# Teensy_Hookup.net
KiCad netlist of a schematic drawn in Altium Designer
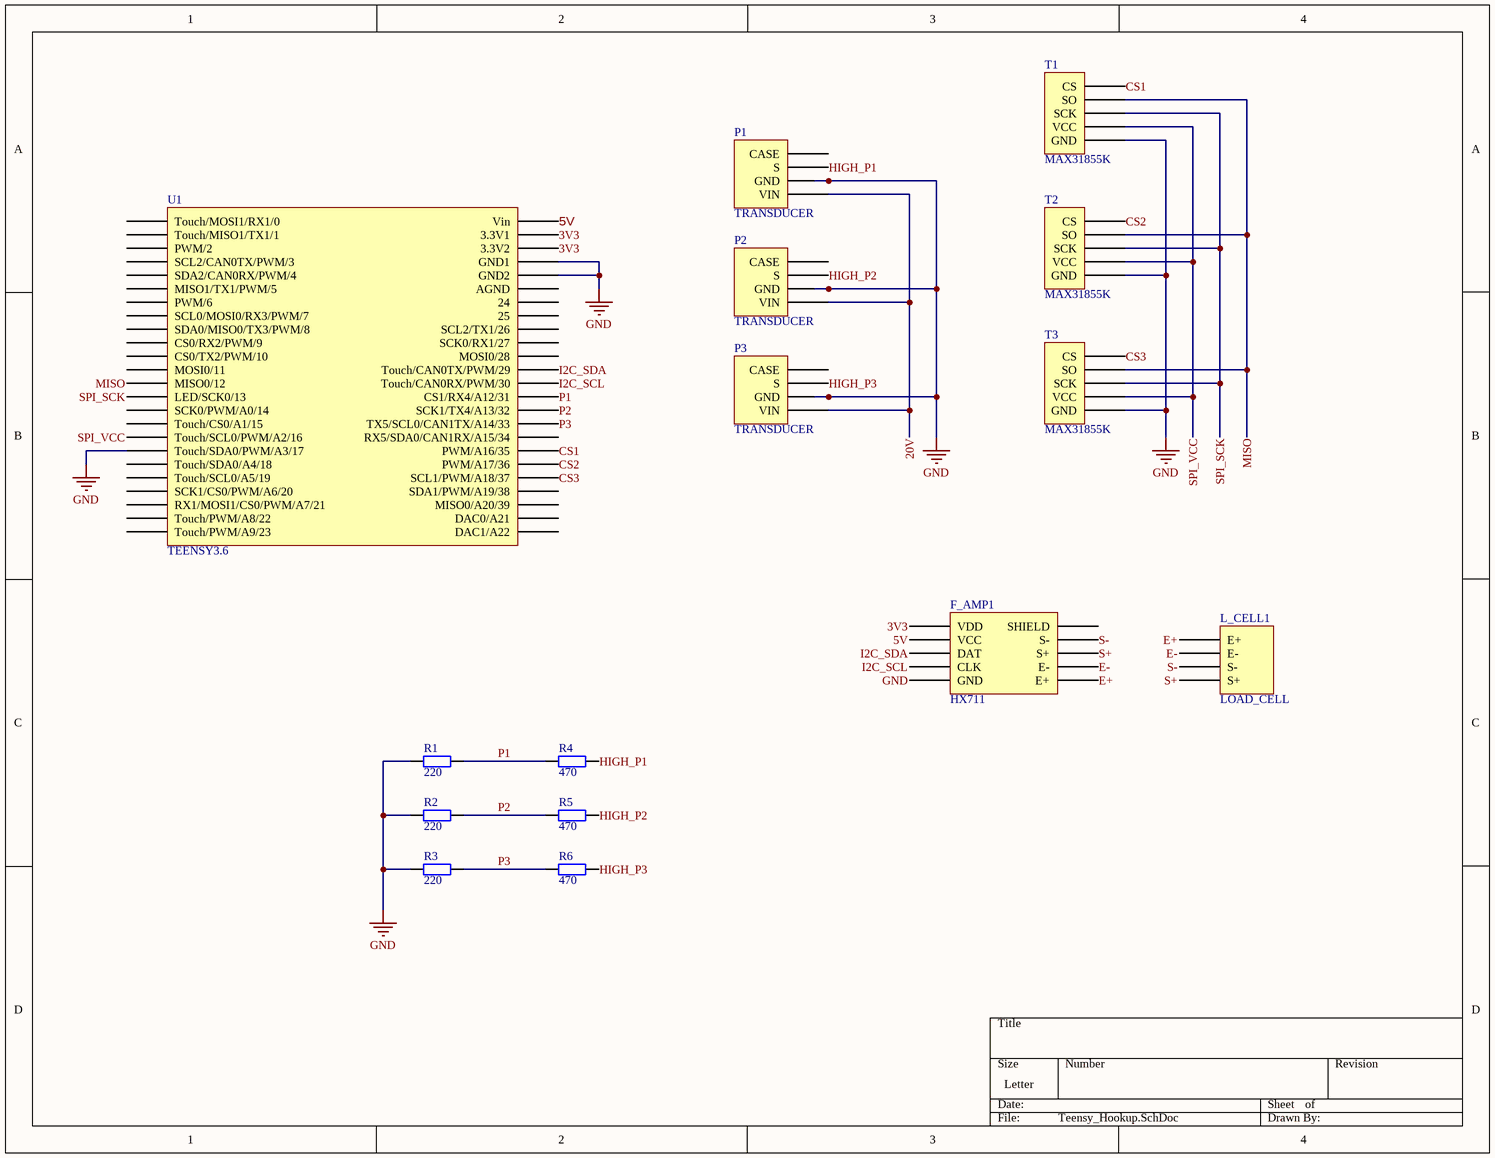
[diagram p0: Teensy_Hookup.SchDoc]

(export (version "E")
  (design (tool "Eeschema 10.0.6"))
  (components
    (comp (ref "F_AMP1") (value "HX711") (libsource (lib "components") (part "HX711")))
    (comp (ref "L_CELL1") (value "LOAD_CELL") (libsource (lib "components") (part "LOAD_CELL")))
    (comp (ref "P1") (value "TRANSDUCER") (libsource (lib "components") (part "TRANSDUCER")))
    (comp (ref "P2") (value "TRANSDUCER") (libsource (lib "components") (part "TRANSDUCER")))
    (comp (ref "P3") (value "TRANSDUCER") (libsource (lib "components") (part "TRANSDUCER")))
    (comp (ref "R1")
      (value "220")
      (footprint "AXIAL-0.4")
      (description "Resistor")
      (fields (field (name "PUBLISHER") "Altium Limited"))
      (libsource (lib "Miscellaneous Devices") (part "Res2"))
    )
    (comp (ref "R2")
      (value "220")
      (footprint "AXIAL-0.4")
      (description "Resistor")
      (fields (field (name "PUBLISHER") "Altium Limited"))
      (libsource (lib "Miscellaneous Devices") (part "Res2"))
    )
    (comp (ref "R3")
      (value "220")
      (footprint "AXIAL-0.4")
      (description "Resistor")
      (fields (field (name "PUBLISHER") "Altium Limited"))
      (libsource (lib "Miscellaneous Devices") (part "Res2"))
    )
    (comp (ref "R4")
      (value "470")
      (footprint "AXIAL-0.4")
      (description "Resistor")
      (fields (field (name "PUBLISHER") "Altium Limited"))
      (libsource (lib "Miscellaneous Devices") (part "Res2"))
    )
    (comp (ref "R5")
      (value "470")
      (footprint "AXIAL-0.4")
      (description "Resistor")
      (fields (field (name "PUBLISHER") "Altium Limited"))
      (libsource (lib "Miscellaneous Devices") (part "Res2"))
    )
    (comp (ref "R6")
      (value "470")
      (footprint "AXIAL-0.4")
      (description "Resistor")
      (fields (field (name "PUBLISHER") "Altium Limited"))
      (libsource (lib "Miscellaneous Devices") (part "Res2"))
    )
    (comp (ref "T1") (value "MAX31855K") (libsource (lib "components") (part "MAX31855K")))
    (comp (ref "T2") (value "MAX31855K") (libsource (lib "components") (part "MAX31855K")))
    (comp (ref "T3") (value "MAX31855K") (libsource (lib "components") (part "MAX31855K")))
    (comp (ref "U1") (value "TEENSY3.6") (libsource (lib "components") (part "TEENSY3.6")))
  )
  (nets
    (net (code "1") (name "/3V3") (class "Default")
      (node (ref "F_AMP1") (pin "1") (pinfunction "VDD_1") (pintype "passive"))
      (node (ref "U1") (pin "3.3V1") (pinfunction "3.3V1_3.3V1") (pintype "power_in"))
      (node (ref "U1") (pin "3.3V2") (pinfunction "3.3V2_3.3V2") (pintype "power_in"))
    )
    (net (code "2") (name "/5V") (class "Default")
      (node (ref "F_AMP1") (pin "2") (pinfunction "VCC_2") (pintype "passive"))
      (node (ref "U1") (pin "VIN") (pinfunction "Vin_VIN") (pintype "power_in"))
    )
    (net (code "3") (name "/20V") (class "Default")
      (node (ref "P1") (pin "1") (pinfunction "VIN_1") (pintype "passive"))
      (node (ref "P2") (pin "1") (pinfunction "VIN_1") (pintype "passive"))
      (node (ref "P3") (pin "1") (pinfunction "VIN_1") (pintype "passive"))
    )
    (net (code "4") (name "/CS1") (class "Default")
      (node (ref "T1") (pin "5") (pinfunction "CS_5") (pintype "passive"))
      (node (ref "U1") (pin "35") (pinfunction "PWM/A16/35_35") (pintype "passive"))
    )
    (net (code "5") (name "/CS2") (class "Default")
      (node (ref "T2") (pin "5") (pinfunction "CS_5") (pintype "passive"))
      (node (ref "U1") (pin "36") (pinfunction "PWM/A17/36_36") (pintype "passive"))
    )
    (net (code "6") (name "/CS3") (class "Default")
      (node (ref "T3") (pin "5") (pinfunction "CS_5") (pintype "passive"))
      (node (ref "U1") (pin "37") (pinfunction "SCL1/PWM/A18/37_37") (pintype "passive"))
    )
    (net (code "7") (name "/E+") (class "Default")
      (node (ref "F_AMP1") (pin "6") (pinfunction "E+_6") (pintype "passive"))
      (node (ref "L_CELL1") (pin "1") (pinfunction "E+_1") (pintype "passive"))
    )
    (net (code "8") (name "/E-") (class "Default")
      (node (ref "F_AMP1") (pin "7") (pinfunction "E-_7") (pintype "passive"))
      (node (ref "L_CELL1") (pin "2") (pinfunction "E-_2") (pintype "passive"))
    )
    (net (code "9") (name "/HIGH_P1") (class "Default")
      (node (ref "P1") (pin "3") (pinfunction "S_3") (pintype "passive"))
      (node (ref "R4") (pin "2") (pinfunction "2_2") (pintype "passive"))
    )
    (net (code "10") (name "/HIGH_P2") (class "Default")
      (node (ref "P2") (pin "3") (pinfunction "S_3") (pintype "passive"))
      (node (ref "R5") (pin "2") (pinfunction "2_2") (pintype "passive"))
    )
    (net (code "11") (name "/HIGH_P3") (class "Default")
      (node (ref "P3") (pin "3") (pinfunction "S_3") (pintype "passive"))
      (node (ref "R6") (pin "2") (pinfunction "2_2") (pintype "passive"))
    )
    (net (code "12") (name "/I2C_SCL") (class "Default")
      (node (ref "F_AMP1") (pin "4") (pinfunction "CLK_4") (pintype "passive"))
      (node (ref "U1") (pin "30") (pinfunction "Touch/CAN0RX/PWM/30_30") (pintype "passive"))
    )
    (net (code "13") (name "/I2C_SDA") (class "Default")
      (node (ref "F_AMP1") (pin "3") (pinfunction "DAT_3") (pintype "passive"))
      (node (ref "U1") (pin "29") (pinfunction "Touch/CAN0TX/PWM/29_29") (pintype "passive"))
    )
    (net (code "14") (name "/MISO") (class "Default")
      (node (ref "T1") (pin "4") (pinfunction "SO_4") (pintype "passive"))
      (node (ref "T2") (pin "4") (pinfunction "SO_4") (pintype "passive"))
      (node (ref "T3") (pin "4") (pinfunction "SO_4") (pintype "passive"))
      (node (ref "U1") (pin "12") (pinfunction "MISO0/12_12") (pintype "passive"))
    )
    (net (code "15") (name "/P1") (class "Default")
      (node (ref "R1") (pin "2") (pinfunction "2_2") (pintype "passive"))
      (node (ref "R4") (pin "1") (pinfunction "1_1") (pintype "passive"))
      (node (ref "U1") (pin "31") (pinfunction "CS1/RX4/A12/31_31") (pintype "passive"))
    )
    (net (code "16") (name "/P2") (class "Default")
      (node (ref "R2") (pin "2") (pinfunction "2_2") (pintype "passive"))
      (node (ref "R5") (pin "1") (pinfunction "1_1") (pintype "passive"))
      (node (ref "U1") (pin "32") (pinfunction "SCK1/TX4/A13/32_32") (pintype "passive"))
    )
    (net (code "17") (name "/P3") (class "Default")
      (node (ref "R3") (pin "2") (pinfunction "2_2") (pintype "passive"))
      (node (ref "R6") (pin "1") (pinfunction "1_1") (pintype "passive"))
      (node (ref "U1") (pin "33") (pinfunction "TX5/SCL0/CAN1TX/A14/33_33") (pintype "passive"))
    )
    (net (code "18") (name "/S+") (class "Default")
      (node (ref "F_AMP1") (pin "8") (pinfunction "S+_8") (pintype "passive"))
      (node (ref "L_CELL1") (pin "4") (pinfunction "S+_4") (pintype "passive"))
    )
    (net (code "19") (name "/S-") (class "Default")
      (node (ref "F_AMP1") (pin "9") (pinfunction "S-_9") (pintype "passive"))
      (node (ref "L_CELL1") (pin "3") (pinfunction "S-_3") (pintype "passive"))
    )
    (net (code "20") (name "/SPI_SCK") (class "Default")
      (node (ref "T1") (pin "3") (pinfunction "SCK_3") (pintype "passive"))
      (node (ref "T2") (pin "3") (pinfunction "SCK_3") (pintype "passive"))
      (node (ref "T3") (pin "3") (pinfunction "SCK_3") (pintype "passive"))
      (node (ref "U1") (pin "13") (pinfunction "LED/SCK0/13_13") (pintype "passive"))
    )
    (net (code "21") (name "/SPI_VCC") (class "Default")
      (node (ref "T1") (pin "2") (pinfunction "VCC_2") (pintype "passive"))
      (node (ref "T2") (pin "2") (pinfunction "VCC_2") (pintype "passive"))
      (node (ref "T3") (pin "2") (pinfunction "VCC_2") (pintype "passive"))
      (node (ref "U1") (pin "16") (pinfunction "Touch/SCL0/PWM/A2/16_16") (pintype "passive"))
    )
    (net (code "22") (name "GND") (class "Default")
      (node (ref "F_AMP1") (pin "5") (pinfunction "GND_5") (pintype "passive"))
      (node (ref "P1") (pin "2") (pinfunction "GND_2") (pintype "passive"))
      (node (ref "P2") (pin "2") (pinfunction "GND_2") (pintype "passive"))
      (node (ref "P3") (pin "2") (pinfunction "GND_2") (pintype "passive"))
      (node (ref "R1") (pin "1") (pinfunction "1_1") (pintype "passive"))
      (node (ref "R2") (pin "1") (pinfunction "1_1") (pintype "passive"))
      (node (ref "R3") (pin "1") (pinfunction "1_1") (pintype "passive"))
      (node (ref "T1") (pin "1") (pinfunction "GND_1") (pintype "passive"))
      (node (ref "T2") (pin "1") (pinfunction "GND_1") (pintype "passive"))
      (node (ref "T3") (pin "1") (pinfunction "GND_1") (pintype "passive"))
      (node (ref "U1") (pin "17") (pinfunction "Touch/SDA0/PWM/A3/17_17") (pintype "passive"))
      (node (ref "U1") (pin "GND1") (pinfunction "GND1_GND1") (pintype "power_in"))
      (node (ref "U1") (pin "GND2") (pinfunction "GND2_GND2") (pintype "power_in"))
    )
    (net (code "23") (name "unconnected-(F_AMP1-SHIELD-Pad10)") (class "Default")
      (node (ref "F_AMP1") (pin "10") (pinfunction "SHIELD_10") (pintype "passive"))
    )
    (net (code "24") (name "unconnected-(P1-CASE-Pad4)") (class "Default")
      (node (ref "P1") (pin "4") (pinfunction "CASE_4") (pintype "passive"))
    )
    (net (code "25") (name "unconnected-(P2-CASE-Pad4)") (class "Default")
      (node (ref "P2") (pin "4") (pinfunction "CASE_4") (pintype "passive"))
    )
    (net (code "26") (name "unconnected-(P3-CASE-Pad4)") (class "Default")
      (node (ref "P3") (pin "4") (pinfunction "CASE_4") (pintype "passive"))
    )
    (net (code "27") (name "unconnected-(U1-CS0{slash}RX2{slash}PWM{slash}9-Pad9)") (class "Default")
      (node (ref "U1") (pin "9") (pinfunction "CS0/RX2/PWM/9_9") (pintype "passive"))
    )
    (net (code "28") (name "unconnected-(U1-CS0{slash}TX2{slash}PWM{slash}10-Pad10)") (class "Default")
      (node (ref "U1") (pin "10") (pinfunction "CS0/TX2/PWM/10_10") (pintype "passive"))
    )
    (net (code "29") (name "unconnected-(U1-DAC0{slash}A21-PadA21)") (class "Default")
      (node (ref "U1") (pin "A21") (pinfunction "DAC0/A21_A21") (pintype "passive"))
    )
    (net (code "30") (name "unconnected-(U1-DAC1{slash}A22-PadA22)") (class "Default")
      (node (ref "U1") (pin "A22") (pinfunction "DAC1/A22_A22") (pintype "passive"))
    )
    (net (code "31") (name "unconnected-(U1-MISO0{slash}A20{slash}39-Pad39)") (class "Default")
      (node (ref "U1") (pin "39") (pinfunction "MISO0/A20/39_39") (pintype "passive"))
    )
    (net (code "32") (name "unconnected-(U1-MISO1{slash}TX1{slash}PWM{slash}5-Pad5)") (class "Default")
      (node (ref "U1") (pin "5") (pinfunction "MISO1/TX1/PWM/5_5") (pintype "passive"))
    )
    (net (code "33") (name "unconnected-(U1-MOSI0{slash}11-Pad11)") (class "Default")
      (node (ref "U1") (pin "11") (pinfunction "MOSI0/11_11") (pintype "passive"))
    )
    (net (code "34") (name "unconnected-(U1-MOSI0{slash}28-Pad28)") (class "Default")
      (node (ref "U1") (pin "28") (pinfunction "MOSI0/28_28") (pintype "passive"))
    )
    (net (code "35") (name "unconnected-(U1-PWM{slash}2-Pad2)") (class "Default")
      (node (ref "U1") (pin "2") (pinfunction "PWM/2_2") (pintype "passive"))
    )
    (net (code "36") (name "unconnected-(U1-PWM{slash}6-Pad6)") (class "Default")
      (node (ref "U1") (pin "6") (pinfunction "PWM/6_6") (pintype "passive"))
    )
    (net (code "37") (name "unconnected-(U1-Pad24)") (class "Default")
      (node (ref "U1") (pin "24") (pinfunction "24_24") (pintype "passive"))
    )
    (net (code "38") (name "unconnected-(U1-Pad25)") (class "Default")
      (node (ref "U1") (pin "25") (pinfunction "25_25") (pintype "passive"))
    )
    (net (code "39") (name "unconnected-(U1-PadAGND)") (class "Default")
      (node (ref "U1") (pin "AGND") (pinfunction "AGND_AGND") (pintype "power_in"))
    )
    (net (code "40") (name "unconnected-(U1-RX1{slash}MOSI1{slash}CS0{slash}PWM{slash}A7{slash}21-Pad21)") (class "Default")
      (node (ref "U1") (pin "21") (pinfunction "RX1/MOSI1/CS0/PWM/A7/21_21") (pintype "passive"))
    )
    (net (code "41") (name "unconnected-(U1-RX5{slash}SDA0{slash}CAN1RX{slash}A15{slash}34-Pad34)") (class "Default")
      (node (ref "U1") (pin "34") (pinfunction "RX5/SDA0/CAN1RX/A15/34_34") (pintype "passive"))
    )
    (net (code "42") (name "unconnected-(U1-SCK0{slash}PWM{slash}A0{slash}14-Pad14)") (class "Default")
      (node (ref "U1") (pin "14") (pinfunction "SCK0/PWM/A0/14_14") (pintype "passive"))
    )
    (net (code "43") (name "unconnected-(U1-SCK0{slash}RX1{slash}27-Pad27)") (class "Default")
      (node (ref "U1") (pin "27") (pinfunction "SCK0/RX1/27_27") (pintype "passive"))
    )
    (net (code "44") (name "unconnected-(U1-SCK1{slash}CS0{slash}PWM{slash}A6{slash}20-Pad20)") (class "Default")
      (node (ref "U1") (pin "20") (pinfunction "SCK1/CS0/PWM/A6/20_20") (pintype "passive"))
    )
    (net (code "45") (name "unconnected-(U1-SCL0{slash}MOSI0{slash}RX3{slash}PWM{slash}7-Pad7)") (class "Default")
      (node (ref "U1") (pin "7") (pinfunction "SCL0/MOSI0/RX3/PWM/7_7") (pintype "passive"))
    )
    (net (code "46") (name "unconnected-(U1-SCL2{slash}CAN0TX{slash}PWM{slash}3-Pad3)") (class "Default")
      (node (ref "U1") (pin "3") (pinfunction "SCL2/CAN0TX/PWM/3_3") (pintype "passive"))
    )
    (net (code "47") (name "unconnected-(U1-SCL2{slash}TX1{slash}26-Pad26)") (class "Default")
      (node (ref "U1") (pin "26") (pinfunction "SCL2/TX1/26_26") (pintype "passive"))
    )
    (net (code "48") (name "unconnected-(U1-SDA0{slash}MISO0{slash}TX3{slash}PWM{slash}8-Pad8)") (class "Default")
      (node (ref "U1") (pin "8") (pinfunction "SDA0/MISO0/TX3/PWM/8_8") (pintype "passive"))
    )
    (net (code "49") (name "unconnected-(U1-SDA1{slash}PWM{slash}A19{slash}38-Pad38)") (class "Default")
      (node (ref "U1") (pin "38") (pinfunction "SDA1/PWM/A19/38_38") (pintype "passive"))
    )
    (net (code "50") (name "unconnected-(U1-SDA2{slash}CAN0RX{slash}PWM{slash}4-Pad4)") (class "Default")
      (node (ref "U1") (pin "4") (pinfunction "SDA2/CAN0RX/PWM/4_4") (pintype "passive"))
    )
    (net (code "51") (name "unconnected-(U1-Touch{slash}CS0{slash}A1{slash}15-Pad15)") (class "Default")
      (node (ref "U1") (pin "15") (pinfunction "Touch/CS0/A1/15_15") (pintype "passive"))
    )
    (net (code "52") (name "unconnected-(U1-Touch{slash}MISO1{slash}TX1{slash}1-Pad1)") (class "Default")
      (node (ref "U1") (pin "1") (pinfunction "Touch/MISO1/TX1/1_1") (pintype "passive"))
    )
    (net (code "53") (name "unconnected-(U1-Touch{slash}MOSI1{slash}RX1{slash}0-Pad0)") (class "Default")
      (node (ref "U1") (pin "0") (pinfunction "Touch/MOSI1/RX1/0_0") (pintype "passive"))
    )
    (net (code "54") (name "unconnected-(U1-Touch{slash}PWM{slash}A8{slash}22-Pad22)") (class "Default")
      (node (ref "U1") (pin "22") (pinfunction "Touch/PWM/A8/22_22") (pintype "passive"))
    )
    (net (code "55") (name "unconnected-(U1-Touch{slash}PWM{slash}A9{slash}23-Pad23)") (class "Default")
      (node (ref "U1") (pin "23") (pinfunction "Touch/PWM/A9/23_23") (pintype "passive"))
    )
    (net (code "56") (name "unconnected-(U1-Touch{slash}SCL0{slash}A5{slash}19-Pad19)") (class "Default")
      (node (ref "U1") (pin "19") (pinfunction "Touch/SCL0/A5/19_19") (pintype "passive"))
    )
    (net (code "57") (name "unconnected-(U1-Touch{slash}SDA0{slash}A4{slash}18-Pad18)") (class "Default")
      (node (ref "U1") (pin "18") (pinfunction "Touch/SDA0/A4/18_18") (pintype "passive"))
    )
  )
)
